# ftdi_decoupling.net
KiCad netlist of a schematic drawn in EAGLE
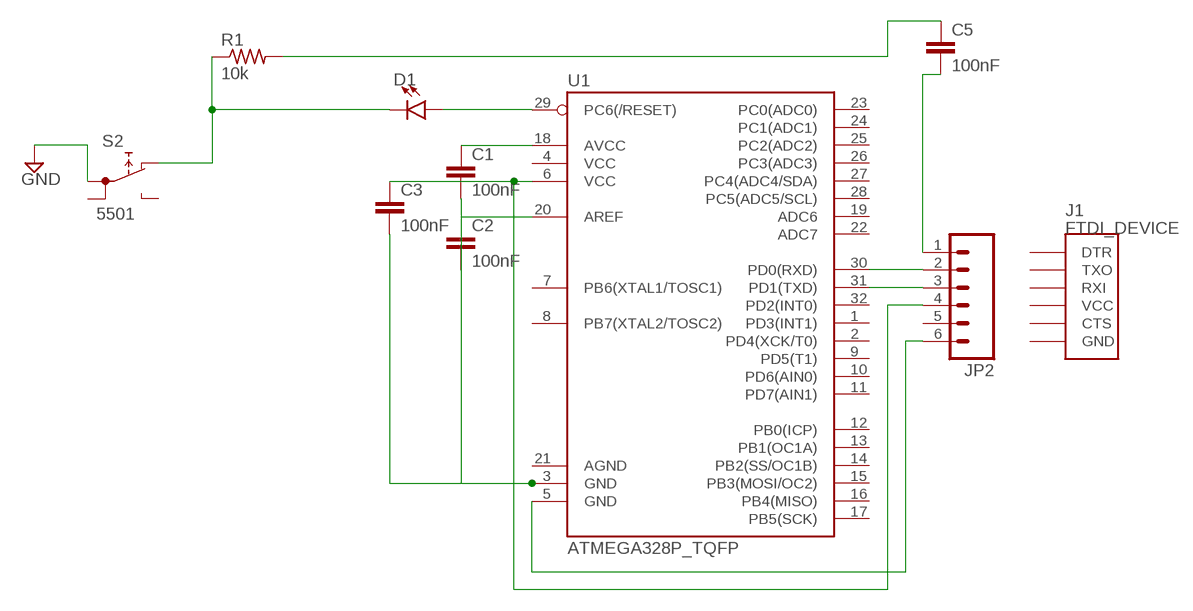
[diagram p0: schematic, sheet 1]

(export (version "E")
  (design (tool "Eeschema 10.0.6"))
  (components
    (comp (ref "C1")
      (value "100nF")
      (footprint "eagle-import:C0603")
      (libsource (lib "eagle-import") (part "C-EUC0603"))
    )
    (comp (ref "C2")
      (value "100nF")
      (footprint "eagle-import:C0603")
      (libsource (lib "eagle-import") (part "C-EUC0603"))
    )
    (comp (ref "C3")
      (value "100nF")
      (footprint "eagle-import:C0603")
      (libsource (lib "eagle-import") (part "C-EUC0603"))
    )
    (comp (ref "C5")
      (value "100nF")
      (footprint "eagle-import:C0603")
      (libsource (lib "eagle-import") (part "C-EUC0603"))
    )
    (comp (ref "D1")
      (value "LED0603")
      (footprint "eagle-import:LED-0603")
      (libsource (lib "eagle-import") (part "LED0603"))
    )
    (comp (ref "J1")
      (value "FTDI_DEVICE")
      (footprint "eagle-import:FTDI_DEVICE_SIDE")
      (libsource (lib "eagle-import") (part "FTDI_DEVICE"))
    )
    (comp (ref "JP2")
      (value "M06SMD-FEMALE-V2")
      (footprint "eagle-import:1X06-SMD-FEMALE-V2")
      (libsource (lib "eagle-import") (part "M06SMD-FEMALE-V2"))
    )
    (comp (ref "R1")
      (value "10k")
      (footprint "eagle-import:R0603")
      (libsource (lib "eagle-import") (part "R-US_R0603"))
    )
    (comp (ref "S2")
      (value "5501")
      (footprint "eagle-import:5501")
      (libsource (lib "eagle-import") (part "55?01"))
    )
    (comp (ref "U1")
      (value "ATMEGA328P_TQFP")
      (footprint "eagle-import:TQFP32-08")
      (libsource (lib "eagle-import") (part "ATMEGA328P_TQFP"))
    )
  )
  (nets
    (net (code "1") (name "GND") (class "Default")
      (node (ref "S2") (pin "1A") (pinfunction "1A_1A") (pintype "passive"))
    )
    (net (code "2") (name "Net-(C1-Pad2)") (class "Default")
      (node (ref "C1") (pin "2") (pinfunction "2_2") (pintype "passive"))
      (node (ref "C2") (pin "2") (pinfunction "2_2") (pintype "passive"))
      (node (ref "C3") (pin "2") (pinfunction "2_2") (pintype "passive"))
      (node (ref "U1") (pin "3") (pinfunction "GND_3") (pintype "bidirectional"))
    )
    (net (code "3") (name "Net-(C3-Pad1)") (class "Default")
      (node (ref "C3") (pin "1") (pinfunction "1_1") (pintype "passive"))
      (node (ref "JP2") (pin "4") (pinfunction "4_4") (pintype "passive"))
      (node (ref "U1") (pin "6") (pinfunction "VCC_6") (pintype "bidirectional"))
    )
    (net (code "4") (name "Net-(C5-Pad1)") (class "Default")
      (node (ref "C5") (pin "1") (pinfunction "1_1") (pintype "passive"))
      (node (ref "R1") (pin "2") (pinfunction "2_2") (pintype "passive"))
    )
    (net (code "5") (name "Net-(C5-Pad2)") (class "Default")
      (node (ref "C5") (pin "2") (pinfunction "2_2") (pintype "passive"))
      (node (ref "JP2") (pin "1") (pinfunction "1_1") (pintype "passive"))
    )
    (net (code "6") (name "Net-(D1-PadC)") (class "Default")
      (node (ref "D1") (pin "C") (pinfunction "C_C") (pintype "passive"))
      (node (ref "R1") (pin "1") (pinfunction "1_1") (pintype "passive"))
      (node (ref "S2") (pin "NC") (pinfunction "NC_NC") (pintype "passive"))
    )
    (net (code "7") (name "Net-(JP2-Pad6)") (class "Default")
      (node (ref "JP2") (pin "6") (pinfunction "6_6") (pintype "passive"))
      (node (ref "U1") (pin "5") (pinfunction "GND_5") (pintype "bidirectional"))
    )
    (net (code "8") (name "Net-(U1-AREF)") (class "Default")
      (node (ref "C2") (pin "1") (pinfunction "1_1") (pintype "passive"))
      (node (ref "U1") (pin "20") (pinfunction "AREF_20") (pintype "bidirectional"))
    )
    (net (code "9") (name "Net-(U1-AVCC)") (class "Default")
      (node (ref "C1") (pin "1") (pinfunction "1_1") (pintype "passive"))
      (node (ref "U1") (pin "18") (pinfunction "AVCC_18") (pintype "bidirectional"))
    )
    (net (code "10") (name "Net-(U1-PC6({slash}RESET))") (class "Default")
      (node (ref "D1") (pin "A") (pinfunction "A_A") (pintype "passive"))
      (node (ref "U1") (pin "29") (pinfunction "PC6(/RESET)_29") (pintype "bidirectional"))
    )
    (net (code "11") (name "Net-(U1-PD0(RXD))") (class "Default")
      (node (ref "JP2") (pin "2") (pinfunction "2_2") (pintype "passive"))
      (node (ref "U1") (pin "30") (pinfunction "PD0(RXD)_30") (pintype "bidirectional"))
    )
    (net (code "12") (name "Net-(U1-PD1(TXD))") (class "Default")
      (node (ref "JP2") (pin "3") (pinfunction "3_3") (pintype "passive"))
      (node (ref "U1") (pin "31") (pinfunction "PD1(TXD)_31") (pintype "bidirectional"))
    )
    (net (code "13") (name "unconnected-(J1-CTS-PadP$5)") (class "Default")
      (node (ref "J1") (pin "P$5") (pinfunction "CTS_P$5") (pintype "bidirectional"))
    )
    (net (code "14") (name "unconnected-(J1-DTR-PadP$1)") (class "Default")
      (node (ref "J1") (pin "P$1") (pinfunction "DTR_P$1") (pintype "bidirectional"))
    )
    (net (code "15") (name "unconnected-(J1-GND-PadP$6)") (class "Default")
      (node (ref "J1") (pin "P$6") (pinfunction "GND_P$6") (pintype "bidirectional"))
    )
    (net (code "16") (name "unconnected-(J1-RXI-PadP$3)") (class "Default")
      (node (ref "J1") (pin "P$3") (pinfunction "RXI_P$3") (pintype "bidirectional"))
    )
    (net (code "17") (name "unconnected-(J1-TXO-PadP$2)") (class "Default")
      (node (ref "J1") (pin "P$2") (pinfunction "TXO_P$2") (pintype "bidirectional"))
    )
    (net (code "18") (name "unconnected-(J1-VCC-PadP$4)") (class "Default")
      (node (ref "J1") (pin "P$4") (pinfunction "VCC_P$4") (pintype "bidirectional"))
    )
    (net (code "19") (name "unconnected-(JP2-Pad5)") (class "Default")
      (node (ref "JP2") (pin "5") (pinfunction "5_5") (pintype "passive"))
    )
    (net (code "20") (name "unconnected-(S2-Pad1B)") (class "Default")
      (node (ref "S2") (pin "1B") (pinfunction "1B_1B") (pintype "passive"))
    )
    (net (code "21") (name "unconnected-(S2-PadNO)") (class "Default")
      (node (ref "S2") (pin "NO") (pinfunction "NO_NO") (pintype "passive"))
    )
    (net (code "22") (name "unconnected-(U1-ADC6-Pad19)") (class "Default")
      (node (ref "U1") (pin "19") (pinfunction "ADC6_19") (pintype "bidirectional"))
    )
    (net (code "23") (name "unconnected-(U1-ADC7-Pad22)") (class "Default")
      (node (ref "U1") (pin "22") (pinfunction "ADC7_22") (pintype "bidirectional"))
    )
    (net (code "24") (name "unconnected-(U1-AGND-Pad21)") (class "Default")
      (node (ref "U1") (pin "21") (pinfunction "AGND_21") (pintype "bidirectional"))
    )
    (net (code "25") (name "unconnected-(U1-PB0(ICP)-Pad12)") (class "Default")
      (node (ref "U1") (pin "12") (pinfunction "PB0(ICP)_12") (pintype "bidirectional"))
    )
    (net (code "26") (name "unconnected-(U1-PB1(OC1A)-Pad13)") (class "Default")
      (node (ref "U1") (pin "13") (pinfunction "PB1(OC1A)_13") (pintype "bidirectional"))
    )
    (net (code "27") (name "unconnected-(U1-PB2(SS{slash}OC1B)-Pad14)") (class "Default")
      (node (ref "U1") (pin "14") (pinfunction "PB2(SS/OC1B)_14") (pintype "bidirectional"))
    )
    (net (code "28") (name "unconnected-(U1-PB3(MOSI{slash}OC2)-Pad15)") (class "Default")
      (node (ref "U1") (pin "15") (pinfunction "PB3(MOSI/OC2)_15") (pintype "bidirectional"))
    )
    (net (code "29") (name "unconnected-(U1-PB4(MISO)-Pad16)") (class "Default")
      (node (ref "U1") (pin "16") (pinfunction "PB4(MISO)_16") (pintype "bidirectional"))
    )
    (net (code "30") (name "unconnected-(U1-PB5(SCK)-Pad17)") (class "Default")
      (node (ref "U1") (pin "17") (pinfunction "PB5(SCK)_17") (pintype "bidirectional"))
    )
    (net (code "31") (name "unconnected-(U1-PB6(XTAL1{slash}TOSC1)-Pad7)") (class "Default")
      (node (ref "U1") (pin "7") (pinfunction "PB6(XTAL1/TOSC1)_7") (pintype "bidirectional"))
    )
    (net (code "32") (name "unconnected-(U1-PB7(XTAL2{slash}TOSC2)-Pad8)") (class "Default")
      (node (ref "U1") (pin "8") (pinfunction "PB7(XTAL2/TOSC2)_8") (pintype "bidirectional"))
    )
    (net (code "33") (name "unconnected-(U1-PC0(ADC0)-Pad23)") (class "Default")
      (node (ref "U1") (pin "23") (pinfunction "PC0(ADC0)_23") (pintype "bidirectional"))
    )
    (net (code "34") (name "unconnected-(U1-PC1(ADC1)-Pad24)") (class "Default")
      (node (ref "U1") (pin "24") (pinfunction "PC1(ADC1)_24") (pintype "bidirectional"))
    )
    (net (code "35") (name "unconnected-(U1-PC2(ADC2)-Pad25)") (class "Default")
      (node (ref "U1") (pin "25") (pinfunction "PC2(ADC2)_25") (pintype "bidirectional"))
    )
    (net (code "36") (name "unconnected-(U1-PC3(ADC3)-Pad26)") (class "Default")
      (node (ref "U1") (pin "26") (pinfunction "PC3(ADC3)_26") (pintype "bidirectional"))
    )
    (net (code "37") (name "unconnected-(U1-PC4(ADC4{slash}SDA)-Pad27)") (class "Default")
      (node (ref "U1") (pin "27") (pinfunction "PC4(ADC4/SDA)_27") (pintype "bidirectional"))
    )
    (net (code "38") (name "unconnected-(U1-PC5(ADC5{slash}SCL)-Pad28)") (class "Default")
      (node (ref "U1") (pin "28") (pinfunction "PC5(ADC5/SCL)_28") (pintype "bidirectional"))
    )
    (net (code "39") (name "unconnected-(U1-PD2(INT0)-Pad32)") (class "Default")
      (node (ref "U1") (pin "32") (pinfunction "PD2(INT0)_32") (pintype "bidirectional"))
    )
    (net (code "40") (name "unconnected-(U1-PD3(INT1)-Pad1)") (class "Default")
      (node (ref "U1") (pin "1") (pinfunction "PD3(INT1)_1") (pintype "bidirectional"))
    )
    (net (code "41") (name "unconnected-(U1-PD4(XCK{slash}T0)-Pad2)") (class "Default")
      (node (ref "U1") (pin "2") (pinfunction "PD4(XCK/T0)_2") (pintype "bidirectional"))
    )
    (net (code "42") (name "unconnected-(U1-PD5(T1)-Pad9)") (class "Default")
      (node (ref "U1") (pin "9") (pinfunction "PD5(T1)_9") (pintype "bidirectional"))
    )
    (net (code "43") (name "unconnected-(U1-PD6(AIN0)-Pad10)") (class "Default")
      (node (ref "U1") (pin "10") (pinfunction "PD6(AIN0)_10") (pintype "bidirectional"))
    )
    (net (code "44") (name "unconnected-(U1-PD7(AIN1)-Pad11)") (class "Default")
      (node (ref "U1") (pin "11") (pinfunction "PD7(AIN1)_11") (pintype "bidirectional"))
    )
    (net (code "45") (name "unconnected-(U1-VCC-Pad4)") (class "Default")
      (node (ref "U1") (pin "4") (pinfunction "VCC_4") (pintype "bidirectional"))
    )
  )
)
